# IF_RX.net
KiCad netlist of a schematic drawn in Altium Designer
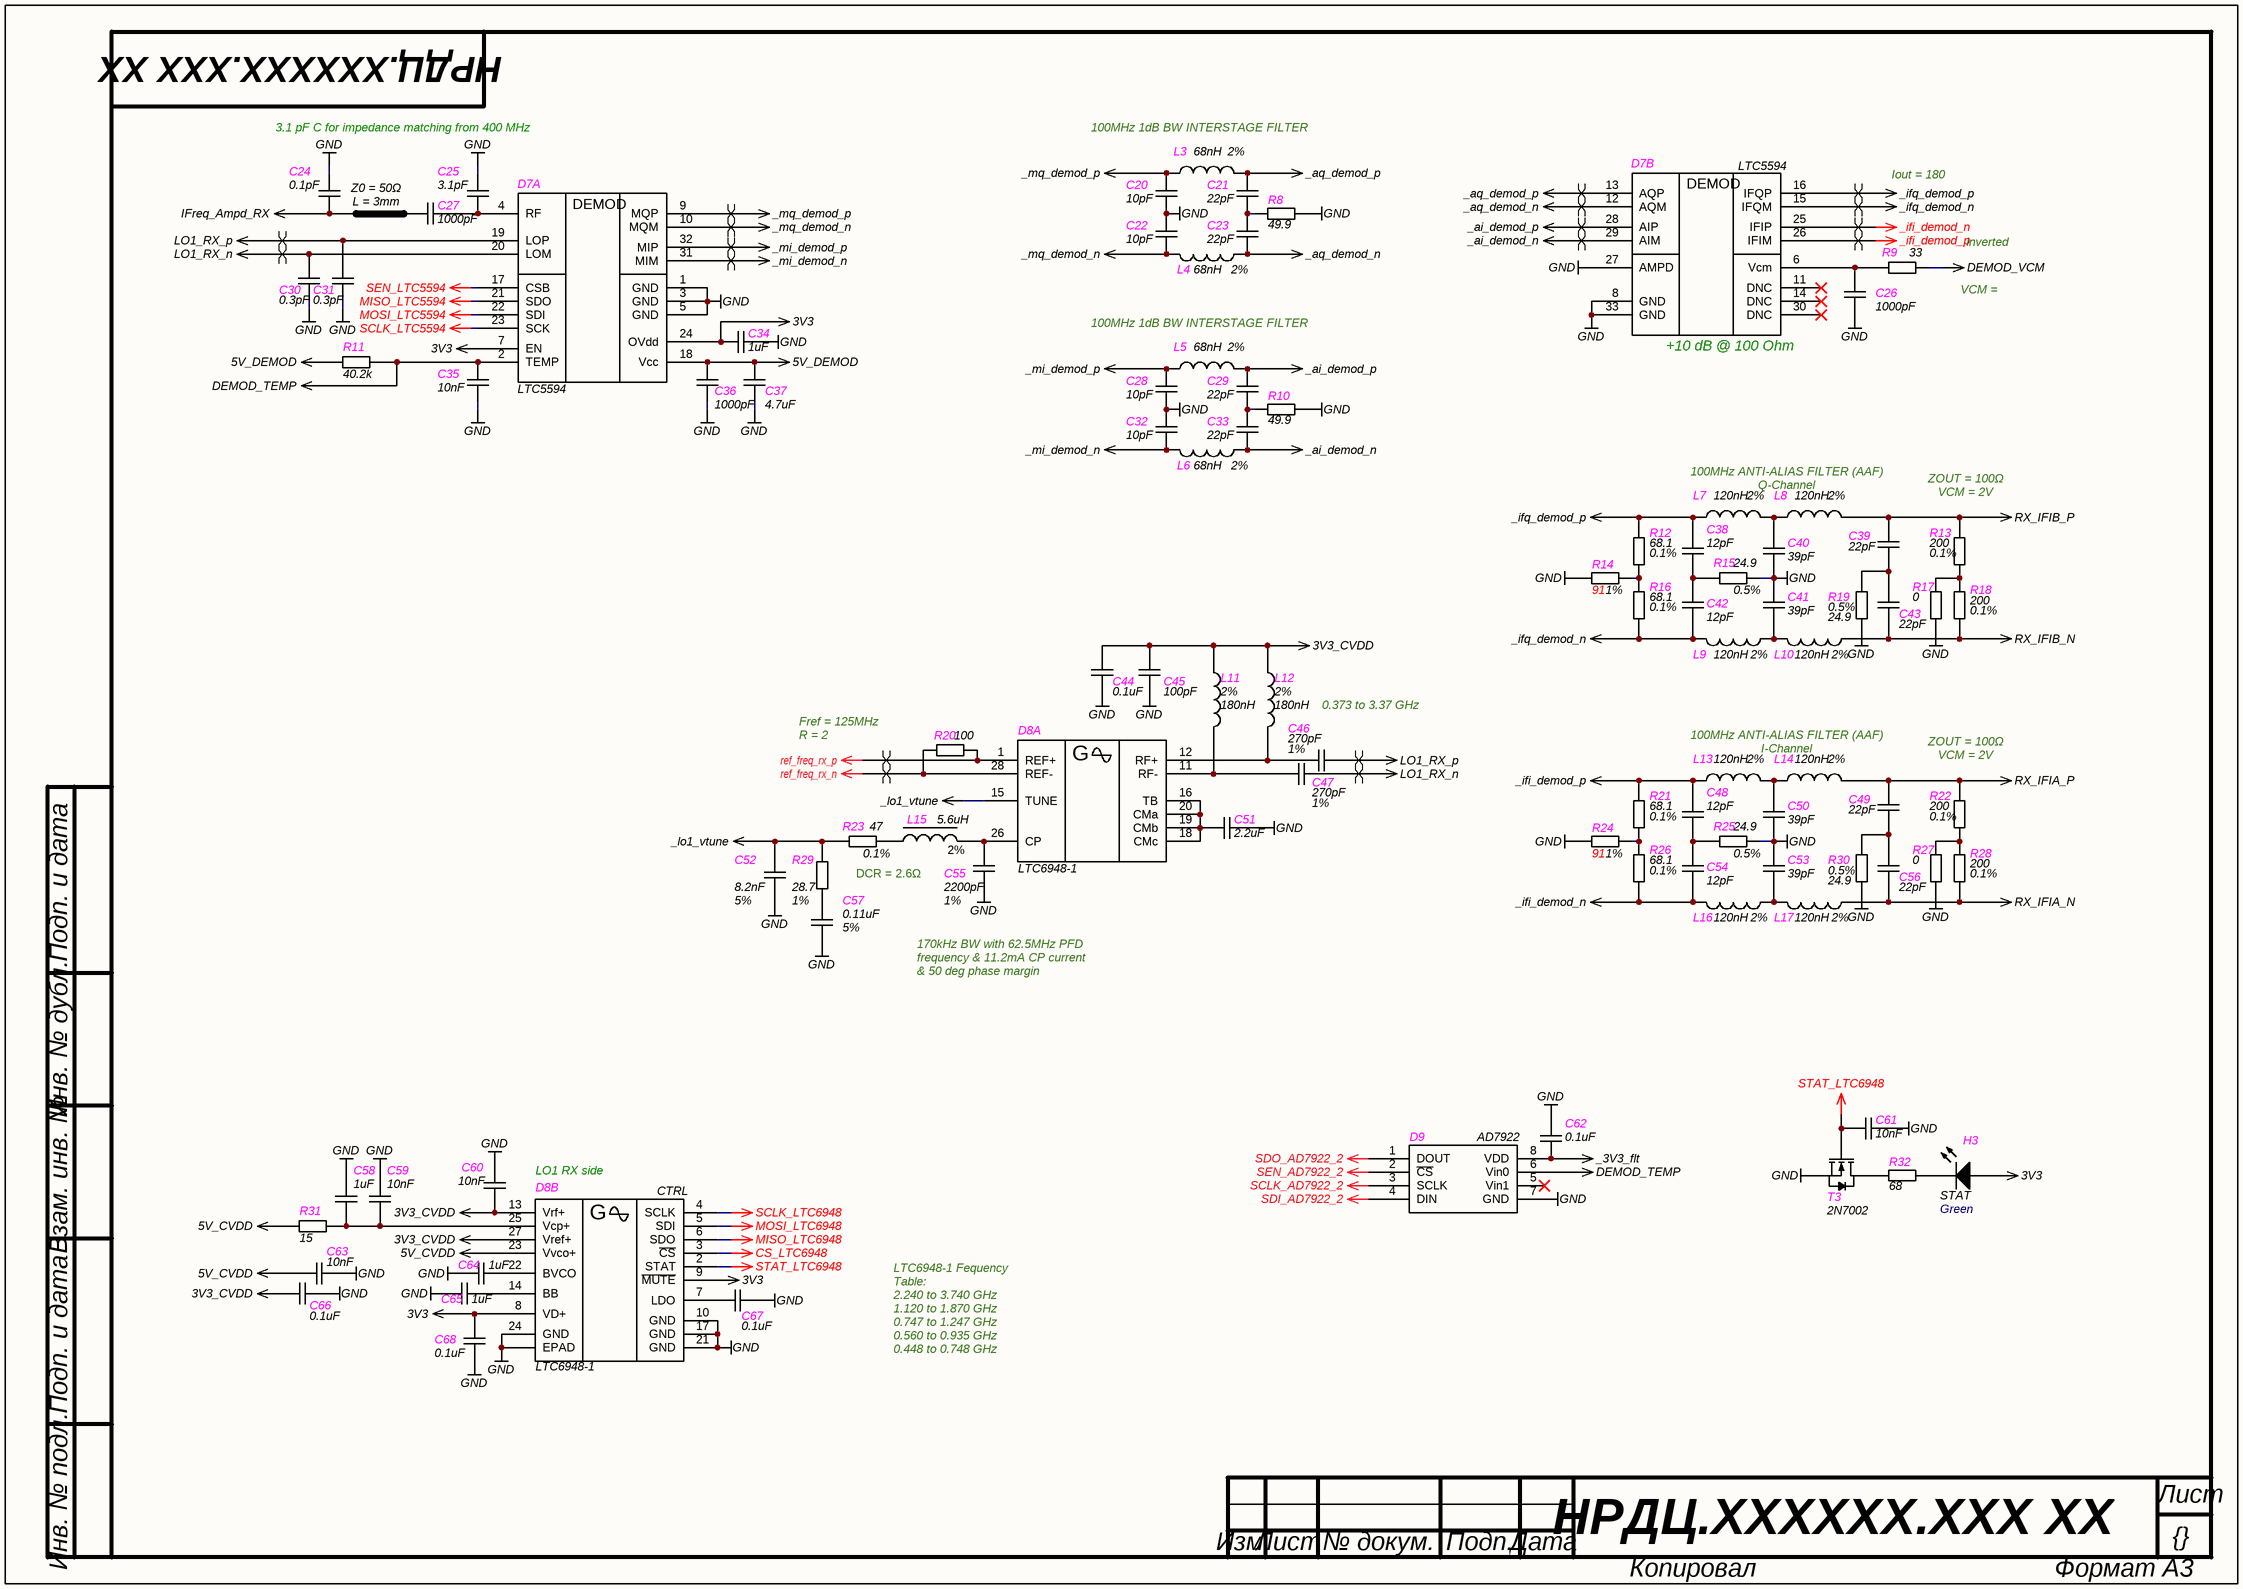
[diagram p0: IF_RX.SchDoc]

(export (version "E")
  (design (tool "Eeschema 10.0.6"))
  (components
    (comp (ref "C20")
      (value "10pF")
      (footprint "C0402")
      (description "SMD Capacitor")
      (fields (field (name "MANUFACTURER") "Murata") (field (name "TOLERANCE") "1%"))
      (libsource (lib "Kintex_SDR") (part "CAP"))
    )
    (comp (ref "C21")
      (value "22pF")
      (footprint "C0402")
      (description "SMD Capacitor")
      (fields (field (name "MANUFACTURER") "Murata") (field (name "TOLERANCE") "1%"))
      (libsource (lib "Kintex_SDR") (part "CAP"))
    )
    (comp (ref "C22")
      (value "10pF")
      (footprint "C0402")
      (description "SMD Capacitor")
      (fields (field (name "MANUFACTURER") "Murata") (field (name "TOLERANCE") "1%"))
      (libsource (lib "Kintex_SDR") (part "CAP"))
    )
    (comp (ref "C23")
      (value "22pF")
      (footprint "C0402")
      (description "SMD Capacitor")
      (fields (field (name "MANUFACTURER") "Murata") (field (name "TOLERANCE") "1%"))
      (libsource (lib "Kintex_SDR") (part "CAP"))
    )
    (comp (ref "C24")
      (value "0.1pF")
      (footprint "C0402")
      (description "SMD Capacitor")
      (fields (field (name "MANUFACTURER") "Murata") (field (name "TOLERANCE") "±0.05pF"))
      (libsource (lib "Kintex_SDR") (part "CAP"))
    )
    (comp (ref "C25")
      (value "3.1pF")
      (footprint "C0402")
      (description "SMD Capacitor")
      (fields (field (name "MANUFACTURER") "Murata") (field (name "TOLERANCE") "±0.05pF"))
      (libsource (lib "Kintex_SDR") (part "CAP"))
    )
    (comp (ref "C26")
      (value "1000pF")
      (footprint "C0402")
      (description "SMD Capacitor")
      (fields (field (name "MANUFACTURER") "Murata") (field (name "TOLERANCE") "5%"))
      (libsource (lib "Kintex_SDR") (part "CAP"))
    )
    (comp (ref "C27")
      (value "1000pF")
      (footprint "C0402")
      (description "SMD Capacitor")
      (fields (field (name "MANUFACTURER") "Murata") (field (name "TOLERANCE") "5%"))
      (libsource (lib "Kintex_SDR") (part "CAP"))
    )
    (comp (ref "C28")
      (value "10pF")
      (footprint "C0402")
      (description "SMD Capacitor")
      (fields (field (name "MANUFACTURER") "Murata") (field (name "TOLERANCE") "1%"))
      (libsource (lib "Kintex_SDR") (part "CAP"))
    )
    (comp (ref "C29")
      (value "22pF")
      (footprint "C0402")
      (description "SMD Capacitor")
      (fields (field (name "MANUFACTURER") "Murata") (field (name "TOLERANCE") "1%"))
      (libsource (lib "Kintex_SDR") (part "CAP"))
    )
    (comp (ref "C30")
      (value "0.3pF")
      (footprint "C0402")
      (description "SMD Capacitor")
      (fields (field (name "MANUFACTURER") "Murata") (field (name "TOLERANCE") "±0.05pF"))
      (libsource (lib "Kintex_SDR") (part "CAP"))
    )
    (comp (ref "C31")
      (value "0.3pF")
      (footprint "C0402")
      (description "SMD Capacitor")
      (fields (field (name "MANUFACTURER") "Murata") (field (name "TOLERANCE") "±0.05pF"))
      (libsource (lib "Kintex_SDR") (part "CAP"))
    )
    (comp (ref "C32")
      (value "10pF")
      (footprint "C0402")
      (description "SMD Capacitor")
      (fields (field (name "MANUFACTURER") "Murata") (field (name "TOLERANCE") "1%"))
      (libsource (lib "Kintex_SDR") (part "CAP"))
    )
    (comp (ref "C33")
      (value "22pF")
      (footprint "C0402")
      (description "SMD Capacitor")
      (fields (field (name "MANUFACTURER") "Murata") (field (name "TOLERANCE") "1%"))
      (libsource (lib "Kintex_SDR") (part "CAP"))
    )
    (comp (ref "C34")
      (value "1uF")
      (footprint "C0402")
      (description "SMD Capacitor")
      (fields (field (name "MANUFACTURER") "Murata") (field (name "TOLERANCE") "10%"))
      (libsource (lib "Kintex_SDR") (part "CAP"))
    )
    (comp (ref "C35")
      (value "10nF")
      (footprint "C0402")
      (description "SMD Capacitor")
      (fields (field (name "MANUFACTURER") "Murata") (field (name "TOLERANCE") "10%"))
      (libsource (lib "Kintex_SDR") (part "CAP"))
    )
    (comp (ref "C36")
      (value "1000pF")
      (footprint "C0402")
      (description "SMD Capacitor")
      (fields (field (name "MANUFACTURER") "Murata") (field (name "TOLERANCE") "5%"))
      (libsource (lib "Kintex_SDR") (part "CAP"))
    )
    (comp (ref "C37")
      (value "4.7uF")
      (footprint "C0805")
      (description "SMD Capacitor")
      (fields (field (name "MANUFACTURER") "Murata") (field (name "TOLERANCE") "10%"))
      (libsource (lib "Kintex_SDR") (part "CAP"))
    )
    (comp (ref "C38")
      (value "12pF")
      (footprint "C0402")
      (description "SMD Capacitor")
      (fields (field (name "MANUFACTURER") "Murata") (field (name "TOLERANCE") "1%"))
      (libsource (lib "Kintex_SDR") (part "CAP"))
    )
    (comp (ref "C39")
      (value "22pF")
      (footprint "C0402")
      (description "SMD Capacitor")
      (fields (field (name "MANUFACTURER") "Murata") (field (name "TOLERANCE") "1%"))
      (libsource (lib "Kintex_SDR") (part "CAP"))
    )
    (comp (ref "C40")
      (value "39pF")
      (footprint "C0402")
      (description "SMD Capacitor")
      (fields (field (name "MANUFACTURER") "Murata") (field (name "TOLERANCE") "1%"))
      (libsource (lib "Kintex_SDR") (part "CAP"))
    )
    (comp (ref "C41")
      (value "39pF")
      (footprint "C0402")
      (description "SMD Capacitor")
      (fields (field (name "MANUFACTURER") "Murata") (field (name "TOLERANCE") "1%"))
      (libsource (lib "Kintex_SDR") (part "CAP"))
    )
    (comp (ref "C42")
      (value "12pF")
      (footprint "C0402")
      (description "SMD Capacitor")
      (fields (field (name "MANUFACTURER") "Murata") (field (name "TOLERANCE") "1%"))
      (libsource (lib "Kintex_SDR") (part "CAP"))
    )
    (comp (ref "C43")
      (value "22pF")
      (footprint "C0402")
      (description "SMD Capacitor")
      (fields (field (name "MANUFACTURER") "Murata") (field (name "TOLERANCE") "1%"))
      (libsource (lib "Kintex_SDR") (part "CAP"))
    )
    (comp (ref "C44")
      (value "0.1uF")
      (footprint "C0402")
      (description "SMD Capacitor")
      (fields (field (name "MANUFACTURER") "Murata") (field (name "TOLERANCE") "10%"))
      (libsource (lib "Kintex_SDR") (part "CAP"))
    )
    (comp (ref "C45")
      (value "100pF")
      (footprint "C0402")
      (description "SMD Capacitor")
      (fields (field (name "MANUFACTURER") "Murata") (field (name "TOLERANCE") "1%"))
      (libsource (lib "Kintex_SDR") (part "CAP"))
    )
    (comp (ref "C46")
      (value "270pF")
      (footprint "C0402")
      (description "SMD Capacitor")
      (fields
        (field (name "MANUFACTURER") "Murata")
        (field (name "TOLERANCE") "1%")
        (field (name "VOLTAGE") "50V")
      )
      (libsource (lib "Kintex_SDR") (part "CAP"))
    )
    (comp (ref "C47")
      (value "270pF")
      (footprint "C0402")
      (description "SMD Capacitor")
      (fields
        (field (name "MANUFACTURER") "Murata")
        (field (name "TOLERANCE") "1%")
        (field (name "VOLTAGE") "50V")
      )
      (libsource (lib "Kintex_SDR") (part "CAP"))
    )
    (comp (ref "C48")
      (value "12pF")
      (footprint "C0402")
      (description "SMD Capacitor")
      (fields (field (name "MANUFACTURER") "Murata") (field (name "TOLERANCE") "1%"))
      (libsource (lib "Kintex_SDR") (part "CAP"))
    )
    (comp (ref "C49")
      (value "22pF")
      (footprint "C0402")
      (description "SMD Capacitor")
      (fields (field (name "MANUFACTURER") "Murata") (field (name "TOLERANCE") "1%"))
      (libsource (lib "Kintex_SDR") (part "CAP"))
    )
    (comp (ref "C50")
      (value "39pF")
      (footprint "C0402")
      (description "SMD Capacitor")
      (fields (field (name "MANUFACTURER") "Murata") (field (name "TOLERANCE") "1%"))
      (libsource (lib "Kintex_SDR") (part "CAP"))
    )
    (comp (ref "C51")
      (value "2.2uF")
      (footprint "C0603")
      (description "SMD Capacitor")
      (fields (field (name "MANUFACTURER") "Murata") (field (name "TOLERANCE") "10%"))
      (libsource (lib "Kintex_SDR") (part "CAP"))
    )
    (comp (ref "C52")
      (value "8.2nF")
      (footprint "C0603")
      (description "SMD Capacitor")
      (fields
        (field (name "MANUFACTURER") "Murata")
        (field (name "TOLERANCE") "5%")
        (field (name "VOLTAGE") "50V")
      )
      (libsource (lib "Kintex_SDR") (part "CAP"))
    )
    (comp (ref "C53")
      (value "39pF")
      (footprint "C0402")
      (description "SMD Capacitor")
      (fields (field (name "MANUFACTURER") "Murata") (field (name "TOLERANCE") "1%"))
      (libsource (lib "Kintex_SDR") (part "CAP"))
    )
    (comp (ref "C54")
      (value "12pF")
      (footprint "C0402")
      (description "SMD Capacitor")
      (fields (field (name "MANUFACTURER") "Murata") (field (name "TOLERANCE") "1%"))
      (libsource (lib "Kintex_SDR") (part "CAP"))
    )
    (comp (ref "C55")
      (value "2200pF")
      (footprint "C0603")
      (description "SMD Capacitor")
      (fields
        (field (name "MANUFACTURER") "Murata")
        (field (name "TOLERANCE") "1%")
        (field (name "VOLTAGE") "50V")
      )
      (libsource (lib "Kintex_SDR") (part "CAP"))
    )
    (comp (ref "C56")
      (value "22pF")
      (footprint "C0402")
      (description "SMD Capacitor")
      (fields (field (name "MANUFACTURER") "Murata") (field (name "TOLERANCE") "1%"))
      (libsource (lib "Kintex_SDR") (part "CAP"))
    )
    (comp (ref "C57")
      (value "0.11uF")
      (footprint "C0805")
      (description "SMD Capacitor")
      (fields
        (field (name "MANUFACTURER") "Murata")
        (field (name "TOLERANCE") "5%")
        (field (name "VOLTAGE") "50V")
      )
      (libsource (lib "Kintex_SDR") (part "CAP"))
    )
    (comp (ref "C58")
      (value "1uF")
      (footprint "C0402")
      (description "SMD Capacitor")
      (fields (field (name "MANUFACTURER") "Murata") (field (name "TOLERANCE") "10%"))
      (libsource (lib "Kintex_SDR") (part "CAP"))
    )
    (comp (ref "C59")
      (value "10nF")
      (footprint "C0402")
      (description "SMD Capacitor")
      (fields (field (name "MANUFACTURER") "Murata") (field (name "TOLERANCE") "10%"))
      (libsource (lib "Kintex_SDR") (part "CAP"))
    )
    (comp (ref "C60")
      (value "10nF")
      (footprint "C0402")
      (description "SMD Capacitor")
      (fields (field (name "MANUFACTURER") "Murata") (field (name "TOLERANCE") "10%"))
      (libsource (lib "Kintex_SDR") (part "CAP"))
    )
    (comp (ref "C61")
      (value "10nF")
      (footprint "C0402")
      (description "SMD Capacitor")
      (fields (field (name "MANUFACTURER") "Murata") (field (name "TOLERANCE") "10%"))
      (libsource (lib "Kintex_SDR") (part "CAP"))
    )
    (comp (ref "C62")
      (value "0.1uF")
      (footprint "C0402")
      (description "SMD Capacitor")
      (fields (field (name "MANUFACTURER") "Murata") (field (name "TOLERANCE") "10%"))
      (libsource (lib "Kintex_SDR") (part "CAP"))
    )
    (comp (ref "C63")
      (value "10nF")
      (footprint "C0402")
      (description "SMD Capacitor")
      (fields (field (name "MANUFACTURER") "Murata") (field (name "TOLERANCE") "10%"))
      (libsource (lib "Kintex_SDR") (part "CAP"))
    )
    (comp (ref "C64")
      (value "1uF")
      (footprint "C0402")
      (description "SMD Capacitor")
      (fields (field (name "MANUFACTURER") "Murata") (field (name "TOLERANCE") "10%"))
      (libsource (lib "Kintex_SDR") (part "CAP"))
    )
    (comp (ref "C65")
      (value "1uF")
      (footprint "C0402")
      (description "SMD Capacitor")
      (fields (field (name "MANUFACTURER") "Murata") (field (name "TOLERANCE") "10%"))
      (libsource (lib "Kintex_SDR") (part "CAP"))
    )
    (comp (ref "C66")
      (value "0.1uF")
      (footprint "C0402")
      (description "SMD Capacitor")
      (fields (field (name "MANUFACTURER") "Murata") (field (name "TOLERANCE") "10%"))
      (libsource (lib "Kintex_SDR") (part "CAP"))
    )
    (comp (ref "C67")
      (value "0.1uF")
      (footprint "C0402")
      (description "SMD Capacitor")
      (fields (field (name "MANUFACTURER") "Murata") (field (name "TOLERANCE") "10%"))
      (libsource (lib "Kintex_SDR") (part "CAP"))
    )
    (comp (ref "C68")
      (value "0.1uF")
      (footprint "C0402")
      (description "SMD Capacitor")
      (fields (field (name "MANUFACTURER") "Murata") (field (name "TOLERANCE") "10%"))
      (libsource (lib "Kintex_SDR") (part "CAP"))
    )
    (comp (ref "D7")
      (value "LTC5594")
      (footprint "DBLib:QFN-32")
      (description "Quadrature Demodulator")
      (fields (field (name "MANUFACTURER") "Analog Devices"))
      (libsource (lib "DBLib") (part "LTC5594"))
    )
    (comp (ref "D8")
      (value "LTC6948-1")
      (footprint "QFN-28")
      (description "The LTC®LTC6948 is a high performance, low noise, 6.39GHz  phase-locked loop (PLL)")
      (fields (field (name "MANUFACTURER") "Linear Technology") (field (name "VOLTAGE") "3.15 V ~ 5.25 V"))
      (libsource (lib "") (part "LTC6948_1"))
    )
    (comp (ref "D9")
      (value "AD7922")
      (footprint "MSOP-8")
      (description "1 MSPS, 10-/12-Bit ADC")
      (fields (field (name "MANUFACTURER") "Analog Device") (field (name "VOLTAGE") "2.35 V to 5.25 V"))
      (libsource (lib "Kintex_SDR") (part "AD79x2"))
    )
    (comp (ref "H3")
      (value "STAT")
      (footprint "LED_0805_Green")
      (description "CHIP LED LAMP")
      (fields (field (name "MANUFACTURER") "Kingbright") (field (name "COLOR") "Green"))
      (libsource (lib "DBLib") (part "LED"))
    )
    (comp (ref "L3")
      (value "68nH")
      (footprint "DBLib:L0402HPH")
      (description "Chip SMD Inductor")
      (fields
        (field (name "MANUFACTURER") "Coilcraft")
        (field (name "TOLERANCE") "2%")
        (field (name "Comment") "Inductor RF")
      )
      (libsource (lib "") (part "Inductor RF_1"))
    )
    (comp (ref "L4")
      (value "68nH")
      (footprint "DBLib:L0402HPH")
      (description "Chip SMD Inductor")
      (fields
        (field (name "MANUFACTURER") "Coilcraft")
        (field (name "TOLERANCE") "2%")
        (field (name "Comment") "Inductor RF")
      )
      (libsource (lib "DBLib") (part "Inductor RF"))
    )
    (comp (ref "L5")
      (value "68nH")
      (footprint "DBLib:L0402HPH")
      (description "Chip SMD Inductor")
      (fields
        (field (name "MANUFACTURER") "Coilcraft")
        (field (name "TOLERANCE") "2%")
        (field (name "Comment") "Inductor RF")
      )
      (libsource (lib "") (part "Inductor RF_1"))
    )
    (comp (ref "L6")
      (value "68nH")
      (footprint "DBLib:L0402HPH")
      (description "Chip SMD Inductor")
      (fields
        (field (name "MANUFACTURER") "Coilcraft")
        (field (name "TOLERANCE") "2%")
        (field (name "Comment") "Inductor RF")
      )
      (libsource (lib "DBLib") (part "Inductor RF"))
    )
    (comp (ref "L7")
      (value "120nH")
      (footprint "DBLib:L0402HPH")
      (description "Chip SMD Inductor")
      (fields
        (field (name "MANUFACTURER") "Coilcraft")
        (field (name "TOLERANCE") "2%")
        (field (name "Comment") "Inductor RF")
      )
      (libsource (lib "") (part "Inductor RF_1"))
    )
    (comp (ref "L8")
      (value "120nH")
      (footprint "DBLib:L0402HPH")
      (description "Chip SMD Inductor")
      (fields
        (field (name "MANUFACTURER") "Coilcraft")
        (field (name "TOLERANCE") "2%")
        (field (name "Comment") "Inductor RF")
      )
      (libsource (lib "") (part "Inductor RF_1"))
    )
    (comp (ref "L9")
      (value "120nH")
      (footprint "DBLib:L0402HPH")
      (description "Chip SMD Inductor")
      (fields
        (field (name "MANUFACTURER") "Coilcraft")
        (field (name "TOLERANCE") "2%")
        (field (name "Comment") "Inductor RF")
      )
      (libsource (lib "DBLib") (part "Inductor RF"))
    )
    (comp (ref "L10")
      (value "120nH")
      (footprint "DBLib:L0402HPH")
      (description "Chip SMD Inductor")
      (fields
        (field (name "MANUFACTURER") "Coilcraft")
        (field (name "TOLERANCE") "2%")
        (field (name "Comment") "Inductor RF")
      )
      (libsource (lib "DBLib") (part "Inductor RF"))
    )
    (comp (ref "L11")
      (value "180nH")
      (footprint "DBLib:L0603_HP")
      (description "Chip SMD Inductor")
      (fields
        (field (name "MANUFACTURER") "Coilcraft")
        (field (name "TOLERANCE") "2%")
        (field (name "Comment") "Inductor RF")
      )
      (libsource (lib "DBLib") (part "Inductor RF"))
    )
    (comp (ref "L12")
      (value "180nH")
      (footprint "DBLib:L0603_HP")
      (description "Chip SMD Inductor")
      (fields
        (field (name "MANUFACTURER") "Coilcraft")
        (field (name "TOLERANCE") "2%")
        (field (name "Comment") "Inductor RF")
      )
      (libsource (lib "DBLib") (part "Inductor RF"))
    )
    (comp (ref "L13")
      (value "120nH")
      (footprint "DBLib:L0402HPH")
      (description "Chip SMD Inductor")
      (fields
        (field (name "MANUFACTURER") "Coilcraft")
        (field (name "TOLERANCE") "2%")
        (field (name "Comment") "Inductor RF")
      )
      (libsource (lib "") (part "Inductor RF_1"))
    )
    (comp (ref "L14")
      (value "120nH")
      (footprint "DBLib:L0402HPH")
      (description "Chip SMD Inductor")
      (fields
        (field (name "MANUFACTURER") "Coilcraft")
        (field (name "TOLERANCE") "2%")
        (field (name "Comment") "Inductor RF")
      )
      (libsource (lib "") (part "Inductor RF_1"))
    )
    (comp (ref "L15")
      (value "5.6uH")
      (footprint "DBLib:L1008_LS")
      (description "Chip SMD Inductor")
      (fields
        (field (name "MANUFACTURER") "Coilcraft")
        (field (name "TOLERANCE") "2%")
        (field (name "Comment") "Inductor")
      )
      (libsource (lib "DBLib") (part "Inductor"))
    )
    (comp (ref "L16")
      (value "120nH")
      (footprint "DBLib:L0402HPH")
      (description "Chip SMD Inductor")
      (fields
        (field (name "MANUFACTURER") "Coilcraft")
        (field (name "TOLERANCE") "2%")
        (field (name "Comment") "Inductor RF")
      )
      (libsource (lib "DBLib") (part "Inductor RF"))
    )
    (comp (ref "L17")
      (value "120nH")
      (footprint "DBLib:L0402HPH")
      (description "Chip SMD Inductor")
      (fields
        (field (name "MANUFACTURER") "Coilcraft")
        (field (name "TOLERANCE") "2%")
        (field (name "Comment") "Inductor RF")
      )
      (libsource (lib "DBLib") (part "Inductor RF"))
    )
    (comp (ref "R8")
      (value "49.9")
      (footprint "R0402")
      (description "SMD Resistor")
      (fields (field (name "POWER") "0.063 Wt") (field (name "TOLERANCE") "0.5%"))
      (libsource (lib "") (part "RES_2"))
    )
    (comp (ref "R9")
      (value "33")
      (footprint "R0402")
      (description "SMD Resistor")
      (fields (field (name "POWER") "0.1 Wt") (field (name "TOLERANCE") "1%"))
      (libsource (lib "") (part "RES_1"))
    )
    (comp (ref "R10")
      (value "49.9")
      (footprint "R0402")
      (description "SMD Resistor")
      (fields (field (name "POWER") "0.063 Wt") (field (name "TOLERANCE") "0.5%"))
      (libsource (lib "") (part "RES_2"))
    )
    (comp (ref "R11")
      (value "40.2k")
      (footprint "R0402")
      (description "SMD Resistor")
      (fields (field (name "POWER") "0.063 Wt") (field (name "TOLERANCE") "1%"))
      (libsource (lib "") (part "RES_2"))
    )
    (comp (ref "R12")
      (value "68.1")
      (footprint "R0402")
      (description "SMD Resistor")
      (fields
        (field (name "POWER") "0.063 Wt")
        (field (name "TOLERANCE") "0.1%")
        (field (name "MANUFACTURER") "Panasonic Electronic Components")
      )
      (libsource (lib "Kintex_SDR") (part "RES"))
    )
    (comp (ref "R13")
      (value "200")
      (footprint "R0402")
      (description "SMD Resistor")
      (fields
        (field (name "POWER") "0.063 Wt")
        (field (name "TOLERANCE") "0.1%")
        (field (name "MANUFACTURER") "Panasonic Electronic Components")
      )
      (libsource (lib "Kintex_SDR") (part "RES"))
    )
    (comp (ref "R14")
      (value "91")
      (footprint "R0402")
      (description "SMD Resistor")
      (fields
        (field (name "POWER") "1/5 Wt")
        (field (name "TOLERANCE") "1%")
        (field (name "MANUFACTURER") "Panasonic Electronic Components")
      )
      (libsource (lib "") (part "RES_2"))
    )
    (comp (ref "R15")
      (value "24.9")
      (footprint "R0402")
      (description "SMD Resistor")
      (fields
        (field (name "POWER") "0.063 Wt")
        (field (name "TOLERANCE") "0.5%")
        (field (name "MANUFACTURER") "Panasonic Electronic Components")
      )
      (libsource (lib "") (part "RES_2"))
    )
    (comp (ref "R16")
      (value "68.1")
      (footprint "R0402")
      (description "SMD Resistor")
      (fields
        (field (name "POWER") "0.063 Wt")
        (field (name "TOLERANCE") "0.1%")
        (field (name "MANUFACTURER") "Panasonic Electronic Components")
      )
      (libsource (lib "Kintex_SDR") (part "RES"))
    )
    (comp (ref "R17")
      (value "0")
      (footprint "R0402")
      (description "SMD Resistor")
      (fields (field (name "POWER") "0.1 Wt") (field (name "TOLERANCE") "1%"))
      (libsource (lib "Kintex_SDR") (part "RES"))
    )
    (comp (ref "R18")
      (value "200")
      (footprint "R0402")
      (description "SMD Resistor")
      (fields
        (field (name "POWER") "0.063 Wt")
        (field (name "TOLERANCE") "0.1%")
        (field (name "MANUFACTURER") "Panasonic Electronic Components")
      )
      (libsource (lib "Kintex_SDR") (part "RES"))
    )
    (comp (ref "R19")
      (value "24.9")
      (footprint "R0402")
      (description "SMD Resistor")
      (fields
        (field (name "POWER") "0.063 Wt")
        (field (name "TOLERANCE") "0.5%")
        (field (name "MANUFACTURER") "Panasonic Electronic Components")
      )
      (libsource (lib "Kintex_SDR") (part "RES"))
    )
    (comp (ref "R20")
      (value "100")
      (footprint "R0402")
      (description "SMD Resistor")
      (fields (field (name "POWER") "0.062 Wt") (field (name "TOLERANCE") "5%"))
      (libsource (lib "") (part "RES_2"))
    )
    (comp (ref "R21")
      (value "68.1")
      (footprint "R0402")
      (description "SMD Resistor")
      (fields
        (field (name "POWER") "0.063 Wt")
        (field (name "TOLERANCE") "0.1%")
        (field (name "MANUFACTURER") "Panasonic Electronic Components")
      )
      (libsource (lib "Kintex_SDR") (part "RES"))
    )
    (comp (ref "R22")
      (value "200")
      (footprint "R0402")
      (description "SMD Resistor")
      (fields
        (field (name "POWER") "0.063 Wt")
        (field (name "TOLERANCE") "0.1%")
        (field (name "MANUFACTURER") "Panasonic Electronic Components")
      )
      (libsource (lib "Kintex_SDR") (part "RES"))
    )
    (comp (ref "R23")
      (value "47")
      (footprint "R0402")
      (description "SMD Resistor")
      (fields
        (field (name "POWER") "0.2 Wt")
        (field (name "TOLERANCE") "0.1%")
        (field (name "MANUFACTURER") "Panasonic Electronic Components")
      )
      (libsource (lib "") (part "RES_1"))
    )
    (comp (ref "R24")
      (value "91")
      (footprint "R0402")
      (description "SMD Resistor")
      (fields
        (field (name "POWER") "1/5 Wt")
        (field (name "TOLERANCE") "1%")
        (field (name "MANUFACTURER") "Panasonic Electronic Components")
      )
      (libsource (lib "") (part "RES_2"))
    )
    (comp (ref "R25")
      (value "24.9")
      (footprint "R0402")
      (description "SMD Resistor")
      (fields
        (field (name "POWER") "0.063 Wt")
        (field (name "TOLERANCE") "0.5%")
        (field (name "MANUFACTURER") "Panasonic Electronic Components")
      )
      (libsource (lib "") (part "RES_2"))
    )
    (comp (ref "R26")
      (value "68.1")
      (footprint "R0402")
      (description "SMD Resistor")
      (fields
        (field (name "POWER") "0.063 Wt")
        (field (name "TOLERANCE") "0.1%")
        (field (name "MANUFACTURER") "Panasonic Electronic Components")
      )
      (libsource (lib "Kintex_SDR") (part "RES"))
    )
    (comp (ref "R27")
      (value "0")
      (footprint "R0402")
      (description "SMD Resistor")
      (fields (field (name "POWER") "0.1 Wt") (field (name "TOLERANCE") "1%"))
      (libsource (lib "Kintex_SDR") (part "RES"))
    )
    (comp (ref "R28")
      (value "200")
      (footprint "R0402")
      (description "SMD Resistor")
      (fields
        (field (name "POWER") "0.063 Wt")
        (field (name "TOLERANCE") "0.1%")
        (field (name "MANUFACTURER") "Panasonic Electronic Components")
      )
      (libsource (lib "Kintex_SDR") (part "RES"))
    )
    (comp (ref "R29")
      (value "28.7")
      (footprint "R0402")
      (description "SMD Resistor")
      (fields
        (field (name "POWER") "0.2 Wt")
        (field (name "TOLERANCE") "1%")
        (field (name "MANUFACTURER") "Panasonic Electronic Components")
      )
      (libsource (lib "Kintex_SDR") (part "RES"))
    )
    (comp (ref "R30")
      (value "24.9")
      (footprint "R0402")
      (description "SMD Resistor")
      (fields
        (field (name "POWER") "0.063 Wt")
        (field (name "TOLERANCE") "0.5%")
        (field (name "MANUFACTURER") "Panasonic Electronic Components")
      )
      (libsource (lib "Kintex_SDR") (part "RES"))
    )
    (comp (ref "R31")
      (value "15")
      (footprint "R0603")
      (description "SMD Resistor")
      (fields (field (name "POWER") "0.1 Wt") (field (name "TOLERANCE") "1%"))
      (libsource (lib "") (part "RES_1"))
    )
    (comp (ref "R32")
      (value "68")
      (footprint "R0402")
      (description "SMD Resistor")
      (fields (field (name "POWER") "0.062 Wt") (field (name "TOLERANCE") "5%"))
      (libsource (lib "") (part "RES_2"))
    )
    (comp (ref "T3")
      (value "2N7002")
      (footprint "SOT-23")
      (description "N-Channel MOSFET 2N7002")
      (fields (field (name "VOLTAGE") "60V"))
      (libsource (lib "Kintex_SDR") (part "2N7002"))
    )
  )
  (nets
    (net (code "1") (name "3V3") (class "Default")
      (node (ref "C34") (pin "1") (pinfunction "1_1") (pintype "passive"))
      (node (ref "C68") (pin "2") (pinfunction "2_2") (pintype "passive"))
      (node (ref "D7") (pin "24") (pinfunction "OVdd_24") (pintype "passive"))
      (node (ref "D7") (pin "7") (pinfunction "EN_7") (pintype "passive"))
      (node (ref "D8") (pin "8") (pinfunction "VD+_8") (pintype "passive"))
      (node (ref "D8") (pin "9") (pinfunction "~{MUTE}_9") (pintype "passive"))
      (node (ref "H3") (pin "2") (pinfunction "A_2") (pintype "passive"))
    )
    (net (code "2") (name "3V3_CVDD") (class "Default")
      (node (ref "C44") (pin "2") (pinfunction "2_2") (pintype "passive"))
      (node (ref "C45") (pin "2") (pinfunction "2_2") (pintype "passive"))
      (node (ref "C60") (pin "2") (pinfunction "2_2") (pintype "passive"))
      (node (ref "C66") (pin "2") (pinfunction "2_2") (pintype "passive"))
      (node (ref "D8") (pin "13") (pinfunction "Vrf+_13") (pintype "passive"))
      (node (ref "D8") (pin "27") (pinfunction "Vref+_27") (pintype "passive"))
      (node (ref "L11") (pin "2") (pinfunction "2_2") (pintype "passive"))
      (node (ref "L12") (pin "2") (pinfunction "2_2") (pintype "passive"))
    )
    (net (code "3") (name "5V_CVDD") (class "Default")
      (node (ref "C63") (pin "1") (pinfunction "1_1") (pintype "passive"))
      (node (ref "D8") (pin "23") (pinfunction "Vvco+_23") (pintype "passive"))
      (node (ref "R31") (pin "2") (pinfunction "2_2") (pintype "passive"))
    )
    (net (code "4") (name "5V_DEMOD") (class "Default")
      (node (ref "C36") (pin "1") (pinfunction "1_1") (pintype "passive"))
      (node (ref "C37") (pin "2") (pinfunction "2_2") (pintype "passive"))
      (node (ref "D7") (pin "18") (pinfunction "Vcc_18") (pintype "passive"))
      (node (ref "R11") (pin "1") (pinfunction "1_1") (pintype "passive"))
    )
    (net (code "5") (name "CS_LTC6948") (class "Default")
      (node (ref "D8") (pin "3") (pinfunction "~{CS}_3") (pintype "passive"))
    )
    (net (code "6") (name "DEMOD_TEMP") (class "Default")
      (node (ref "C35") (pin "1") (pinfunction "1_1") (pintype "passive"))
      (node (ref "D7") (pin "2") (pinfunction "TEMP_2") (pintype "passive"))
      (node (ref "D9") (pin "6") (pinfunction "Vin0_6") (pintype "passive"))
      (node (ref "R11") (pin "2") (pinfunction "2_2") (pintype "passive"))
    )
    (net (code "7") (name "DEMOD_VCM") (class "Default")
      (node (ref "R9") (pin "1") (pinfunction "1_1") (pintype "passive"))
    )
    (net (code "8") (name "GND") (class "Default")
      (node (ref "C20") (pin "2") (pinfunction "2_2") (pintype "passive"))
      (node (ref "C22") (pin "1") (pinfunction "1_1") (pintype "passive"))
      (node (ref "C24") (pin "2") (pinfunction "2_2") (pintype "passive"))
      (node (ref "C25") (pin "2") (pinfunction "2_2") (pintype "passive"))
      (node (ref "C26") (pin "2") (pinfunction "2_2") (pintype "passive"))
      (node (ref "C28") (pin "2") (pinfunction "2_2") (pintype "passive"))
      (node (ref "C30") (pin "2") (pinfunction "2_2") (pintype "passive"))
      (node (ref "C31") (pin "2") (pinfunction "2_2") (pintype "passive"))
      (node (ref "C32") (pin "1") (pinfunction "1_1") (pintype "passive"))
      (node (ref "C34") (pin "2") (pinfunction "2_2") (pintype "passive"))
      (node (ref "C35") (pin "2") (pinfunction "2_2") (pintype "passive"))
      (node (ref "C36") (pin "2") (pinfunction "2_2") (pintype "passive"))
      (node (ref "C37") (pin "1") (pinfunction "1_1") (pintype "passive"))
      (node (ref "C40") (pin "2") (pinfunction "2_2") (pintype "passive"))
      (node (ref "C41") (pin "1") (pinfunction "1_1") (pintype "passive"))
      (node (ref "C44") (pin "1") (pinfunction "1_1") (pintype "passive"))
      (node (ref "C45") (pin "1") (pinfunction "1_1") (pintype "passive"))
      (node (ref "C50") (pin "2") (pinfunction "2_2") (pintype "passive"))
      (node (ref "C51") (pin "1") (pinfunction "1_1") (pintype "passive"))
      (node (ref "C52") (pin "1") (pinfunction "1_1") (pintype "passive"))
      (node (ref "C53") (pin "1") (pinfunction "1_1") (pintype "passive"))
      (node (ref "C55") (pin "1") (pinfunction "1_1") (pintype "passive"))
      (node (ref "C57") (pin "1") (pinfunction "1_1") (pintype "passive"))
      (node (ref "C58") (pin "1") (pinfunction "1_1") (pintype "passive"))
      (node (ref "C59") (pin "1") (pinfunction "1_1") (pintype "passive"))
      (node (ref "C60") (pin "1") (pinfunction "1_1") (pintype "passive"))
      (node (ref "C61") (pin "2") (pinfunction "2_2") (pintype "passive"))
      (node (ref "C62") (pin "2") (pinfunction "2_2") (pintype "passive"))
      (node (ref "C63") (pin "2") (pinfunction "2_2") (pintype "passive"))
      (node (ref "C64") (pin "1") (pinfunction "1_1") (pintype "passive"))
      (node (ref "C65") (pin "2") (pinfunction "2_2") (pintype "passive"))
      (node (ref "C66") (pin "1") (pinfunction "1_1") (pintype "passive"))
      (node (ref "C67") (pin "1") (pinfunction "1_1") (pintype "passive"))
      (node (ref "C68") (pin "1") (pinfunction "1_1") (pintype "passive"))
      (node (ref "D7") (pin "1") (pinfunction "GND_1") (pintype "passive"))
      (node (ref "D7") (pin "27") (pinfunction "AMPD_27") (pintype "passive"))
      (node (ref "D7") (pin "3") (pinfunction "GND_3") (pintype "passive"))
      (node (ref "D7") (pin "33") (pinfunction "GND_33") (pintype "passive"))
      (node (ref "D7") (pin "5") (pinfunction "GND_5") (pintype "passive"))
      (node (ref "D7") (pin "8") (pinfunction "GND_8") (pintype "passive"))
      (node (ref "D8") (pin "10") (pinfunction "GND_10") (pintype "passive"))
      (node (ref "D8") (pin "17") (pinfunction "GND_17") (pintype "passive"))
      (node (ref "D8") (pin "21") (pinfunction "GND_21") (pintype "passive"))
      (node (ref "D8") (pin "24") (pinfunction "GND_24") (pintype "passive"))
      (node (ref "D8") (pin "29") (pinfunction "EPAD_29") (pintype "passive"))
      (node (ref "D9") (pin "7") (pinfunction "GND_7") (pintype "passive"))
      (node (ref "R10") (pin "2") (pinfunction "2_2") (pintype "passive"))
      (node (ref "R14") (pin "1") (pinfunction "1_1") (pintype "passive"))
      (node (ref "R15") (pin "2") (pinfunction "2_2") (pintype "passive"))
      (node (ref "R17") (pin "2") (pinfunction "2_2") (pintype "passive"))
      (node (ref "R19") (pin "2") (pinfunction "2_2") (pintype "passive"))
      (node (ref "R24") (pin "1") (pinfunction "1_1") (pintype "passive"))
      (node (ref "R25") (pin "2") (pinfunction "2_2") (pintype "passive"))
      (node (ref "R27") (pin "2") (pinfunction "2_2") (pintype "passive"))
      (node (ref "R30") (pin "2") (pinfunction "2_2") (pintype "passive"))
      (node (ref "R8") (pin "2") (pinfunction "2_2") (pintype "passive"))
      (node (ref "T3") (pin "2") (pinfunction "S_2") (pintype "passive"))
    )
    (net (code "9") (name "IFreq_Ampd_RX") (class "Default")
      (node (ref "C24") (pin "1") (pinfunction "1_1") (pintype "passive"))
      (node (ref "C27") (pin "2") (pinfunction "2_2") (pintype "passive"))
    )
    (net (code "10") (name "LO1_RX_n") (class "Default")
      (node (ref "C30") (pin "1") (pinfunction "1_1") (pintype "passive"))
      (node (ref "C47") (pin "2") (pinfunction "2_2") (pintype "passive"))
      (node (ref "D7") (pin "20") (pinfunction "LOM_20") (pintype "passive"))
    )
    (net (code "11") (name "LO1_RX_p") (class "Default")
      (node (ref "C31") (pin "1") (pinfunction "1_1") (pintype "passive"))
      (node (ref "C46") (pin "2") (pinfunction "2_2") (pintype "passive"))
      (node (ref "D7") (pin "19") (pinfunction "LOP_19") (pintype "passive"))
    )
    (net (code "12") (name "MISO_LTC5594") (class "Default")
      (node (ref "D7") (pin "21") (pinfunction "SDO_21") (pintype "passive"))
    )
    (net (code "13") (name "MISO_LTC6948") (class "Default")
      (node (ref "D8") (pin "6") (pinfunction "SDO_6") (pintype "passive"))
    )
    (net (code "14") (name "MOSI_LTC5594") (class "Default")
      (node (ref "D7") (pin "22") (pinfunction "SDI_22") (pintype "passive"))
    )
    (net (code "15") (name "MOSI_LTC6948") (class "Default")
      (node (ref "D8") (pin "5") (pinfunction "SDI_5") (pintype "passive"))
    )
    (net (code "16") (name "Net-(C21-Pad2)") (class "Default")
      (node (ref "C21") (pin "2") (pinfunction "2_2") (pintype "passive"))
      (node (ref "C23") (pin "1") (pinfunction "1_1") (pintype "passive"))
      (node (ref "R8") (pin "1") (pinfunction "1_1") (pintype "passive"))
    )
    (net (code "17") (name "Net-(C29-Pad2)") (class "Default")
      (node (ref "C29") (pin "2") (pinfunction "2_2") (pintype "passive"))
      (node (ref "C33") (pin "1") (pinfunction "1_1") (pintype "passive"))
      (node (ref "R10") (pin "1") (pinfunction "1_1") (pintype "passive"))
    )
    (net (code "18") (name "Net-(C38-Pad2)") (class "Default")
      (node (ref "C38") (pin "2") (pinfunction "2_2") (pintype "passive"))
      (node (ref "C42") (pin "1") (pinfunction "1_1") (pintype "passive"))
      (node (ref "R15") (pin "1") (pinfunction "1_1") (pintype "passive"))
    )
    (net (code "19") (name "Net-(C39-Pad2)") (class "Default")
      (node (ref "C39") (pin "2") (pinfunction "2_2") (pintype "passive"))
      (node (ref "C43") (pin "1") (pinfunction "1_1") (pintype "passive"))
      (node (ref "R19") (pin "1") (pinfunction "1_1") (pintype "passive"))
    )
    (net (code "20") (name "Net-(C40-Pad1)") (class "Default")
      (node (ref "C40") (pin "1") (pinfunction "1_1") (pintype "passive"))
      (node (ref "L7") (pin "2") (pinfunction "2_2") (pintype "passive"))
      (node (ref "L8") (pin "1") (pinfunction "1_1") (pintype "passive"))
    )
    (net (code "21") (name "Net-(C41-Pad2)") (class "Default")
      (node (ref "C41") (pin "2") (pinfunction "2_2") (pintype "passive"))
      (node (ref "L10") (pin "1") (pinfunction "1_1") (pintype "passive"))
      (node (ref "L9") (pin "2") (pinfunction "2_2") (pintype "passive"))
    )
    (net (code "22") (name "Net-(C48-Pad2)") (class "Default")
      (node (ref "C48") (pin "2") (pinfunction "2_2") (pintype "passive"))
      (node (ref "C54") (pin "1") (pinfunction "1_1") (pintype "passive"))
      (node (ref "R25") (pin "1") (pinfunction "1_1") (pintype "passive"))
    )
    (net (code "23") (name "Net-(C49-Pad2)") (class "Default")
      (node (ref "C49") (pin "2") (pinfunction "2_2") (pintype "passive"))
      (node (ref "C56") (pin "1") (pinfunction "1_1") (pintype "passive"))
      (node (ref "R30") (pin "1") (pinfunction "1_1") (pintype "passive"))
    )
    (net (code "24") (name "Net-(C50-Pad1)") (class "Default")
      (node (ref "C50") (pin "1") (pinfunction "1_1") (pintype "passive"))
      (node (ref "L13") (pin "2") (pinfunction "2_2") (pintype "passive"))
      (node (ref "L14") (pin "1") (pinfunction "1_1") (pintype "passive"))
    )
    (net (code "25") (name "Net-(C53-Pad2)") (class "Default")
      (node (ref "C53") (pin "2") (pinfunction "2_2") (pintype "passive"))
      (node (ref "L16") (pin "2") (pinfunction "2_2") (pintype "passive"))
      (node (ref "L17") (pin "1") (pinfunction "1_1") (pintype "passive"))
    )
    (net (code "26") (name "Net-(C57-Pad2)") (class "Default")
      (node (ref "C57") (pin "2") (pinfunction "2_2") (pintype "passive"))
      (node (ref "R29") (pin "2") (pinfunction "2_2") (pintype "passive"))
    )
    (net (code "27") (name "Net-(D7A-RF)") (class "Default")
      (node (ref "C25") (pin "1") (pinfunction "1_1") (pintype "passive"))
      (node (ref "C27") (pin "1") (pinfunction "1_1") (pintype "passive"))
      (node (ref "D7") (pin "4") (pinfunction "RF_4") (pintype "passive"))
    )
    (net (code "28") (name "Net-(D7B-Vcm)") (class "Default")
      (node (ref "C26") (pin "1") (pinfunction "1_1") (pintype "passive"))
      (node (ref "D7") (pin "6") (pinfunction "Vcm_6") (pintype "passive"))
      (node (ref "R9") (pin "2") (pinfunction "2_2") (pintype "passive"))
    )
    (net (code "29") (name "Net-(D8A-CMa)") (class "Default")
      (node (ref "C51") (pin "2") (pinfunction "2_2") (pintype "passive"))
      (node (ref "D8") (pin "16") (pinfunction "TB_16") (pintype "passive"))
      (node (ref "D8") (pin "18") (pinfunction "CMc_18") (pintype "passive"))
      (node (ref "D8") (pin "19") (pinfunction "CMb_19") (pintype "passive"))
      (node (ref "D8") (pin "20") (pinfunction "CMa_20") (pintype "passive"))
    )
    (net (code "30") (name "Net-(D8A-CP)") (class "Default")
      (node (ref "C55") (pin "2") (pinfunction "2_2") (pintype "passive"))
      (node (ref "D8") (pin "26") (pinfunction "CP_26") (pintype "passive"))
      (node (ref "L15") (pin "2") (pinfunction "2_2") (pintype "passive"))
    )
    (net (code "31") (name "Net-(D8A-RF+)") (class "Default")
      (node (ref "C46") (pin "1") (pinfunction "1_1") (pintype "passive"))
      (node (ref "D8") (pin "12") (pinfunction "RF+_12") (pintype "passive"))
      (node (ref "L12") (pin "1") (pinfunction "1_1") (pintype "passive"))
    )
    (net (code "32") (name "Net-(D8A-RF-)") (class "Default")
      (node (ref "C47") (pin "1") (pinfunction "1_1") (pintype "passive"))
      (node (ref "D8") (pin "11") (pinfunction "RF-_11") (pintype "passive"))
      (node (ref "L11") (pin "1") (pinfunction "1_1") (pintype "passive"))
    )
    (net (code "33") (name "Net-(D8B-BB)") (class "Default")
      (node (ref "C65") (pin "1") (pinfunction "1_1") (pintype "passive"))
      (node (ref "D8") (pin "14") (pinfunction "BB_14") (pintype "passive"))
    )
    (net (code "34") (name "Net-(D8B-BVCO)") (class "Default")
      (node (ref "C64") (pin "2") (pinfunction "2_2") (pintype "passive"))
      (node (ref "D8") (pin "22") (pinfunction "BVCO_22") (pintype "passive"))
    )
    (net (code "35") (name "Net-(D8B-LDO)") (class "Default")
      (node (ref "C67") (pin "2") (pinfunction "2_2") (pintype "passive"))
      (node (ref "D8") (pin "7") (pinfunction "LDO_7") (pintype "passive"))
    )
    (net (code "36") (name "Net-(D8B-Vcp+)") (class "Default")
      (node (ref "C58") (pin "2") (pinfunction "2_2") (pintype "passive"))
      (node (ref "C59") (pin "2") (pinfunction "2_2") (pintype "passive"))
      (node (ref "D8") (pin "25") (pinfunction "Vcp+_25") (pintype "passive"))
      (node (ref "R31") (pin "1") (pinfunction "1_1") (pintype "passive"))
    )
    (net (code "37") (name "Net-(H3-K)") (class "Default")
      (node (ref "H3") (pin "1") (pinfunction "K_1") (pintype "passive"))
      (node (ref "R32") (pin "2") (pinfunction "2_2") (pintype "passive"))
    )
    (net (code "38") (name "Net-(L15-Pad1)") (class "Default")
      (node (ref "L15") (pin "1") (pinfunction "1_1") (pintype "passive"))
      (node (ref "R23") (pin "1") (pinfunction "1_1") (pintype "passive"))
    )
    (net (code "39") (name "Net-(R12-Pad2)") (class "Default")
      (node (ref "R12") (pin "2") (pinfunction "2_2") (pintype "passive"))
      (node (ref "R14") (pin "2") (pinfunction "2_2") (pintype "passive"))
      (node (ref "R16") (pin "1") (pinfunction "1_1") (pintype "passive"))
    )
    (net (code "40") (name "Net-(R13-Pad2)") (class "Default")
      (node (ref "R13") (pin "2") (pinfunction "2_2") (pintype "passive"))
      (node (ref "R17") (pin "1") (pinfunction "1_1") (pintype "passive"))
      (node (ref "R18") (pin "1") (pinfunction "1_1") (pintype "passive"))
    )
    (net (code "41") (name "Net-(R21-Pad2)") (class "Default")
      (node (ref "R21") (pin "2") (pinfunction "2_2") (pintype "passive"))
      (node (ref "R24") (pin "2") (pinfunction "2_2") (pintype "passive"))
      (node (ref "R26") (pin "1") (pinfunction "1_1") (pintype "passive"))
    )
    (net (code "42") (name "Net-(R22-Pad2)") (class "Default")
      (node (ref "R22") (pin "2") (pinfunction "2_2") (pintype "passive"))
      (node (ref "R27") (pin "1") (pinfunction "1_1") (pintype "passive"))
      (node (ref "R28") (pin "1") (pinfunction "1_1") (pintype "passive"))
    )
    (net (code "43") (name "Net-(T3-D)") (class "Default")
      (node (ref "R32") (pin "1") (pinfunction "1_1") (pintype "passive"))
      (node (ref "T3") (pin "3") (pinfunction "D_3") (pintype "passive"))
    )
    (net (code "44") (name "RX_IFIA_N") (class "Default")
      (node (ref "C56") (pin "2") (pinfunction "2_2") (pintype "passive"))
      (node (ref "L17") (pin "2") (pinfunction "2_2") (pintype "passive"))
      (node (ref "R28") (pin "2") (pinfunction "2_2") (pintype "passive"))
    )
    (net (code "45") (name "RX_IFIA_P") (class "Default")
      (node (ref "C49") (pin "1") (pinfunction "1_1") (pintype "passive"))
      (node (ref "L14") (pin "2") (pinfunction "2_2") (pintype "passive"))
      (node (ref "R22") (pin "1") (pinfunction "1_1") (pintype "passive"))
    )
    (net (code "46") (name "RX_IFIB_N") (class "Default")
      (node (ref "C43") (pin "2") (pinfunction "2_2") (pintype "passive"))
      (node (ref "L10") (pin "2") (pinfunction "2_2") (pintype "passive"))
      (node (ref "R18") (pin "2") (pinfunction "2_2") (pintype "passive"))
    )
    (net (code "47") (name "RX_IFIB_P") (class "Default")
      (node (ref "C39") (pin "1") (pinfunction "1_1") (pintype "passive"))
      (node (ref "L8") (pin "2") (pinfunction "2_2") (pintype "passive"))
      (node (ref "R13") (pin "1") (pinfunction "1_1") (pintype "passive"))
    )
    (net (code "48") (name "SCLK_AD7922_2") (class "Default")
      (node (ref "D9") (pin "3") (pinfunction "SCLK_3") (pintype "passive"))
    )
    (net (code "49") (name "SCLK_LTC5594") (class "Default")
      (node (ref "D7") (pin "23") (pinfunction "SCK_23") (pintype "passive"))
    )
    (net (code "50") (name "SCLK_LTC6948") (class "Default")
      (node (ref "D8") (pin "4") (pinfunction "SCLK_4") (pintype "passive"))
    )
    (net (code "51") (name "SDI_AD7922_2") (class "Default")
      (node (ref "D9") (pin "4") (pinfunction "DIN_4") (pintype "passive"))
    )
    (net (code "52") (name "SDO_AD7922_2") (class "Default")
      (node (ref "D9") (pin "1") (pinfunction "DOUT_1") (pintype "passive"))
    )
    (net (code "53") (name "SEN_AD7922_2") (class "Default")
      (node (ref "D9") (pin "2") (pinfunction "~{CS}_2") (pintype "passive"))
    )
    (net (code "54") (name "SEN_LTC5594") (class "Default")
      (node (ref "D7") (pin "17") (pinfunction "CSB_17") (pintype "passive"))
    )
    (net (code "55") (name "STAT_LTC6948") (class "Default")
      (node (ref "C61") (pin "1") (pinfunction "1_1") (pintype "passive"))
      (node (ref "D8") (pin "2") (pinfunction "STAT_2") (pintype "passive"))
      (node (ref "T3") (pin "1") (pinfunction "G_1") (pintype "passive"))
    )
    (net (code "56") (name "_3V3_flt") (class "Default")
      (node (ref "C62") (pin "1") (pinfunction "1_1") (pintype "passive"))
      (node (ref "D9") (pin "8") (pinfunction "VDD_8") (pintype "passive"))
    )
    (net (code "57") (name "_ai_demod_n") (class "Default")
      (node (ref "C33") (pin "2") (pinfunction "2_2") (pintype "passive"))
      (node (ref "D7") (pin "29") (pinfunction "AIM_29") (pintype "passive"))
      (node (ref "L6") (pin "2") (pinfunction "2_2") (pintype "passive"))
    )
    (net (code "58") (name "_ai_demod_p") (class "Default")
      (node (ref "C29") (pin "1") (pinfunction "1_1") (pintype "passive"))
      (node (ref "D7") (pin "28") (pinfunction "AIP_28") (pintype "passive"))
      (node (ref "L5") (pin "2") (pinfunction "2_2") (pintype "passive"))
    )
    (net (code "59") (name "_aq_demod_n") (class "Default")
      (node (ref "C23") (pin "2") (pinfunction "2_2") (pintype "passive"))
      (node (ref "D7") (pin "12") (pinfunction "AQM_12") (pintype "passive"))
      (node (ref "L4") (pin "2") (pinfunction "2_2") (pintype "passive"))
    )
    (net (code "60") (name "_aq_demod_p") (class "Default")
      (node (ref "C21") (pin "1") (pinfunction "1_1") (pintype "passive"))
      (node (ref "D7") (pin "13") (pinfunction "AQP_13") (pintype "passive"))
      (node (ref "L3") (pin "2") (pinfunction "2_2") (pintype "passive"))
    )
    (net (code "61") (name "_ifi_demod_n") (class "Default")
      (node (ref "C54") (pin "2") (pinfunction "2_2") (pintype "passive"))
      (node (ref "D7") (pin "25") (pinfunction "IFIP_25") (pintype "passive"))
      (node (ref "L16") (pin "1") (pinfunction "1_1") (pintype "passive"))
      (node (ref "R26") (pin "2") (pinfunction "2_2") (pintype "passive"))
    )
    (net (code "62") (name "_ifi_demod_p") (class "Default")
      (node (ref "C48") (pin "1") (pinfunction "1_1") (pintype "passive"))
      (node (ref "D7") (pin "26") (pinfunction "IFIM_26") (pintype "passive"))
      (node (ref "L13") (pin "1") (pinfunction "1_1") (pintype "passive"))
      (node (ref "R21") (pin "1") (pinfunction "1_1") (pintype "passive"))
    )
    (net (code "63") (name "_ifq_demod_n") (class "Default")
      (node (ref "C42") (pin "2") (pinfunction "2_2") (pintype "passive"))
      (node (ref "D7") (pin "15") (pinfunction "IFQM_15") (pintype "passive"))
      (node (ref "L9") (pin "1") (pinfunction "1_1") (pintype "passive"))
      (node (ref "R16") (pin "2") (pinfunction "2_2") (pintype "passive"))
    )
    (net (code "64") (name "_ifq_demod_p") (class "Default")
      (node (ref "C38") (pin "1") (pinfunction "1_1") (pintype "passive"))
      (node (ref "D7") (pin "16") (pinfunction "IFQP_16") (pintype "passive"))
      (node (ref "L7") (pin "1") (pinfunction "1_1") (pintype "passive"))
      (node (ref "R12") (pin "1") (pinfunction "1_1") (pintype "passive"))
    )
    (net (code "65") (name "_lo1_vtune") (class "Default")
      (node (ref "C52") (pin "2") (pinfunction "2_2") (pintype "passive"))
      (node (ref "D8") (pin "15") (pinfunction "TUNE_15") (pintype "passive"))
      (node (ref "R23") (pin "2") (pinfunction "2_2") (pintype "passive"))
      (node (ref "R29") (pin "1") (pinfunction "1_1") (pintype "passive"))
    )
    (net (code "66") (name "_mi_demod_n") (class "Default")
      (node (ref "C32") (pin "2") (pinfunction "2_2") (pintype "passive"))
      (node (ref "D7") (pin "31") (pinfunction "MIM_31") (pintype "passive"))
      (node (ref "L6") (pin "1") (pinfunction "1_1") (pintype "passive"))
    )
    (net (code "67") (name "_mi_demod_p") (class "Default")
      (node (ref "C28") (pin "1") (pinfunction "1_1") (pintype "passive"))
      (node (ref "D7") (pin "32") (pinfunction "MIP_32") (pintype "passive"))
      (node (ref "L5") (pin "1") (pinfunction "1_1") (pintype "passive"))
    )
    (net (code "68") (name "_mq_demod_n") (class "Default")
      (node (ref "C22") (pin "2") (pinfunction "2_2") (pintype "passive"))
      (node (ref "D7") (pin "10") (pinfunction "MQM_10") (pintype "passive"))
      (node (ref "L4") (pin "1") (pinfunction "1_1") (pintype "passive"))
    )
    (net (code "69") (name "_mq_demod_p") (class "Default")
      (node (ref "C20") (pin "1") (pinfunction "1_1") (pintype "passive"))
      (node (ref "D7") (pin "9") (pinfunction "MQP_9") (pintype "passive"))
      (node (ref "L3") (pin "1") (pinfunction "1_1") (pintype "passive"))
    )
    (net (code "70") (name "ref_freq_rx_n") (class "Default")
      (node (ref "D8") (pin "28") (pinfunction "REF-_28") (pintype "passive"))
      (node (ref "R20") (pin "1") (pinfunction "1_1") (pintype "passive"))
    )
    (net (code "71") (name "ref_freq_rx_p") (class "Default")
      (node (ref "D8") (pin "1") (pinfunction "REF+_1") (pintype "passive"))
      (node (ref "R20") (pin "2") (pinfunction "2_2") (pintype "passive"))
    )
    (net (code "72") (name "unconnected-(D7B-DNC-Pad11)") (class "Default")
      (node (ref "D7") (pin "11") (pinfunction "DNC_11") (pintype "passive+no_connect"))
    )
    (net (code "73") (name "unconnected-(D7B-DNC-Pad14)") (class "Default")
      (node (ref "D7") (pin "14") (pinfunction "DNC_14") (pintype "passive+no_connect"))
    )
    (net (code "74") (name "unconnected-(D7B-DNC-Pad30)") (class "Default")
      (node (ref "D7") (pin "30") (pinfunction "DNC_30") (pintype "passive+no_connect"))
    )
    (net (code "75") (name "unconnected-(D9-Vin1-Pad5)") (class "Default")
      (node (ref "D9") (pin "5") (pinfunction "Vin1_5") (pintype "passive+no_connect"))
    )
  )
)
